# GPS.net
KiCad netlist of a schematic drawn in Altium Designer
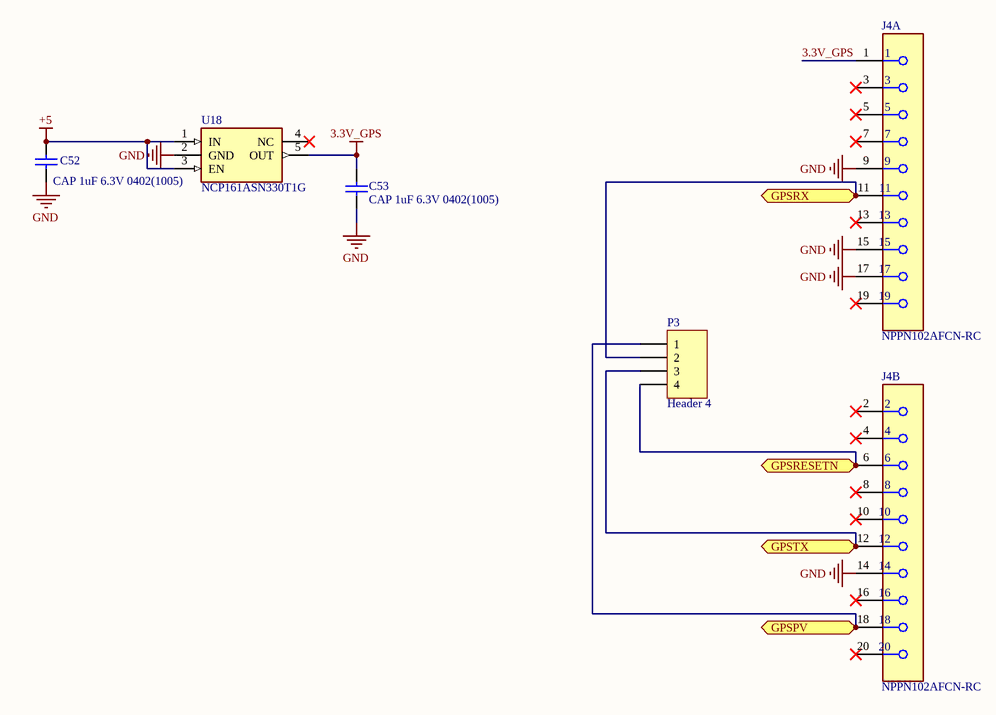
[diagram p0: GPS.SchDoc]

(export (version "E")
  (design (tool "Eeschema 10.0.6"))
  (components
    (comp (ref "C52")
      (value "CAP 1uF 6.3V 0402(1005)")
      (footprint "CAPC0402(1005)60_L")
      (description "CAP 1uF 6.3V ±10% 0402 (1005 Metric) Thickness 0.6mm SMD")
      (fields (field (name "TOLERANCE") "Â±10%"))
      (libsource (lib "Altium Content Vault") (part "CAP"))
    )
    (comp (ref "C53")
      (value "CAP 1uF 6.3V 0402(1005)")
      (footprint "CAPC0402(1005)60_L")
      (description "CAP 1uF 6.3V ±10% 0402 (1005 Metric) Thickness 0.6mm SMD")
      (fields (field (name "TOLERANCE") "Â±10%"))
      (libsource (lib "Altium Content Vault") (part "CAP"))
    )
    (comp (ref "J4")
      (value "NPPN102AFCN-RC")
      (footprint "FP-NPPN102AFCN-RC-MFG")
      (description "CONN HDR 20POS 0.079 GOLD PCB")
      (libsource (lib "Altium Content Vault") (part "5470f601c5e65ab6590c9ba9991e5c7"))
    )
    (comp (ref "P3")
      (value "Header 4")
      (footprint "HDR1X4")
      (description "Header, 4-Pin")
      (fields (field (name "PUBLISHER") "Altium Limited"))
      (libsource (lib "Miscellaneous Connectors") (part "Header 4"))
    )
    (comp (ref "U18")
      (value "NCP161ASN330T1G")
      (footprint "SamacSys:SOT95P280X145-5N")
      (description "Power Supply")
      (fields (field (name "MOUSER PART NUMBER") "863-NCP161ASN330T1G"))
      (libsource (lib "*") (part "NCP161ASN330T1G"))
    )
  )
  (nets
    (net (code "1") (name "+5") (class "Default")
      (node (ref "C52") (pin "2") (pinfunction "2_2") (pintype "passive"))
      (node (ref "U18") (pin "1") (pinfunction "IN_1") (pintype "input"))
      (node (ref "U18") (pin "3") (pinfunction "EN_3") (pintype "input"))
    )
    (net (code "2") (name "/GPSPV") (class "Default")
      (node (ref "J4") (pin "18") (pinfunction "18_18") (pintype "passive"))
      (node (ref "P3") (pin "1") (pinfunction "1_1") (pintype "passive"))
    )
    (net (code "3") (name "/GPSRESETN") (class "Default")
      (node (ref "J4") (pin "6") (pinfunction "6_6") (pintype "passive"))
      (node (ref "P3") (pin "4") (pinfunction "4_4") (pintype "passive"))
    )
    (net (code "4") (name "/GPSRX") (class "Default")
      (node (ref "J4") (pin "11") (pinfunction "11_11") (pintype "passive"))
      (node (ref "P3") (pin "2") (pinfunction "2_2") (pintype "passive"))
    )
    (net (code "5") (name "/GPSTX") (class "Default")
      (node (ref "J4") (pin "12") (pinfunction "12_12") (pintype "passive"))
      (node (ref "P3") (pin "3") (pinfunction "3_3") (pintype "passive"))
    )
    (net (code "6") (name "3.3V_GPS") (class "Default")
      (node (ref "C53") (pin "2") (pinfunction "2_2") (pintype "passive"))
      (node (ref "J4") (pin "1") (pinfunction "1_1") (pintype "passive"))
      (node (ref "U18") (pin "5") (pinfunction "OUT_5") (pintype "output"))
    )
    (net (code "7") (name "GND") (class "Default")
      (node (ref "C52") (pin "1") (pinfunction "1_1") (pintype "passive"))
      (node (ref "C53") (pin "1") (pinfunction "1_1") (pintype "passive"))
      (node (ref "J4") (pin "14") (pinfunction "14_14") (pintype "passive"))
      (node (ref "J4") (pin "15") (pinfunction "15_15") (pintype "passive"))
      (node (ref "J4") (pin "17") (pinfunction "17_17") (pintype "passive"))
      (node (ref "J4") (pin "9") (pinfunction "9_9") (pintype "passive"))
      (node (ref "U18") (pin "2") (pinfunction "GND_2") (pintype "power_in"))
    )
    (net (code "8") (name "unconnected-(J4-Pad2)") (class "Default")
      (node (ref "J4") (pin "2") (pinfunction "2_2") (pintype "passive+no_connect"))
    )
    (net (code "9") (name "unconnected-(J4-Pad3)") (class "Default")
      (node (ref "J4") (pin "3") (pinfunction "3_3") (pintype "passive+no_connect"))
    )
    (net (code "10") (name "unconnected-(J4-Pad4)") (class "Default")
      (node (ref "J4") (pin "4") (pinfunction "4_4") (pintype "passive+no_connect"))
    )
    (net (code "11") (name "unconnected-(J4-Pad5)") (class "Default")
      (node (ref "J4") (pin "5") (pinfunction "5_5") (pintype "passive+no_connect"))
    )
    (net (code "12") (name "unconnected-(J4-Pad7)") (class "Default")
      (node (ref "J4") (pin "7") (pinfunction "7_7") (pintype "passive+no_connect"))
    )
    (net (code "13") (name "unconnected-(J4-Pad8)") (class "Default")
      (node (ref "J4") (pin "8") (pinfunction "8_8") (pintype "passive+no_connect"))
    )
    (net (code "14") (name "unconnected-(J4-Pad10)") (class "Default")
      (node (ref "J4") (pin "10") (pinfunction "10_10") (pintype "passive+no_connect"))
    )
    (net (code "15") (name "unconnected-(J4-Pad13)") (class "Default")
      (node (ref "J4") (pin "13") (pinfunction "13_13") (pintype "passive+no_connect"))
    )
    (net (code "16") (name "unconnected-(J4-Pad16)") (class "Default")
      (node (ref "J4") (pin "16") (pinfunction "16_16") (pintype "passive+no_connect"))
    )
    (net (code "17") (name "unconnected-(J4-Pad19)") (class "Default")
      (node (ref "J4") (pin "19") (pinfunction "19_19") (pintype "passive+no_connect"))
    )
    (net (code "18") (name "unconnected-(J4-Pad20)") (class "Default")
      (node (ref "J4") (pin "20") (pinfunction "20_20") (pintype "passive+no_connect"))
    )
    (net (code "19") (name "unconnected-(U18-NC-Pad4)") (class "Default")
      (node (ref "U18") (pin "4") (pinfunction "NC_4") (pintype "passive+no_connect"))
    )
  )
)
